# MB1296-STLINK.net
KiCad netlist of a schematic drawn in Altium Designer
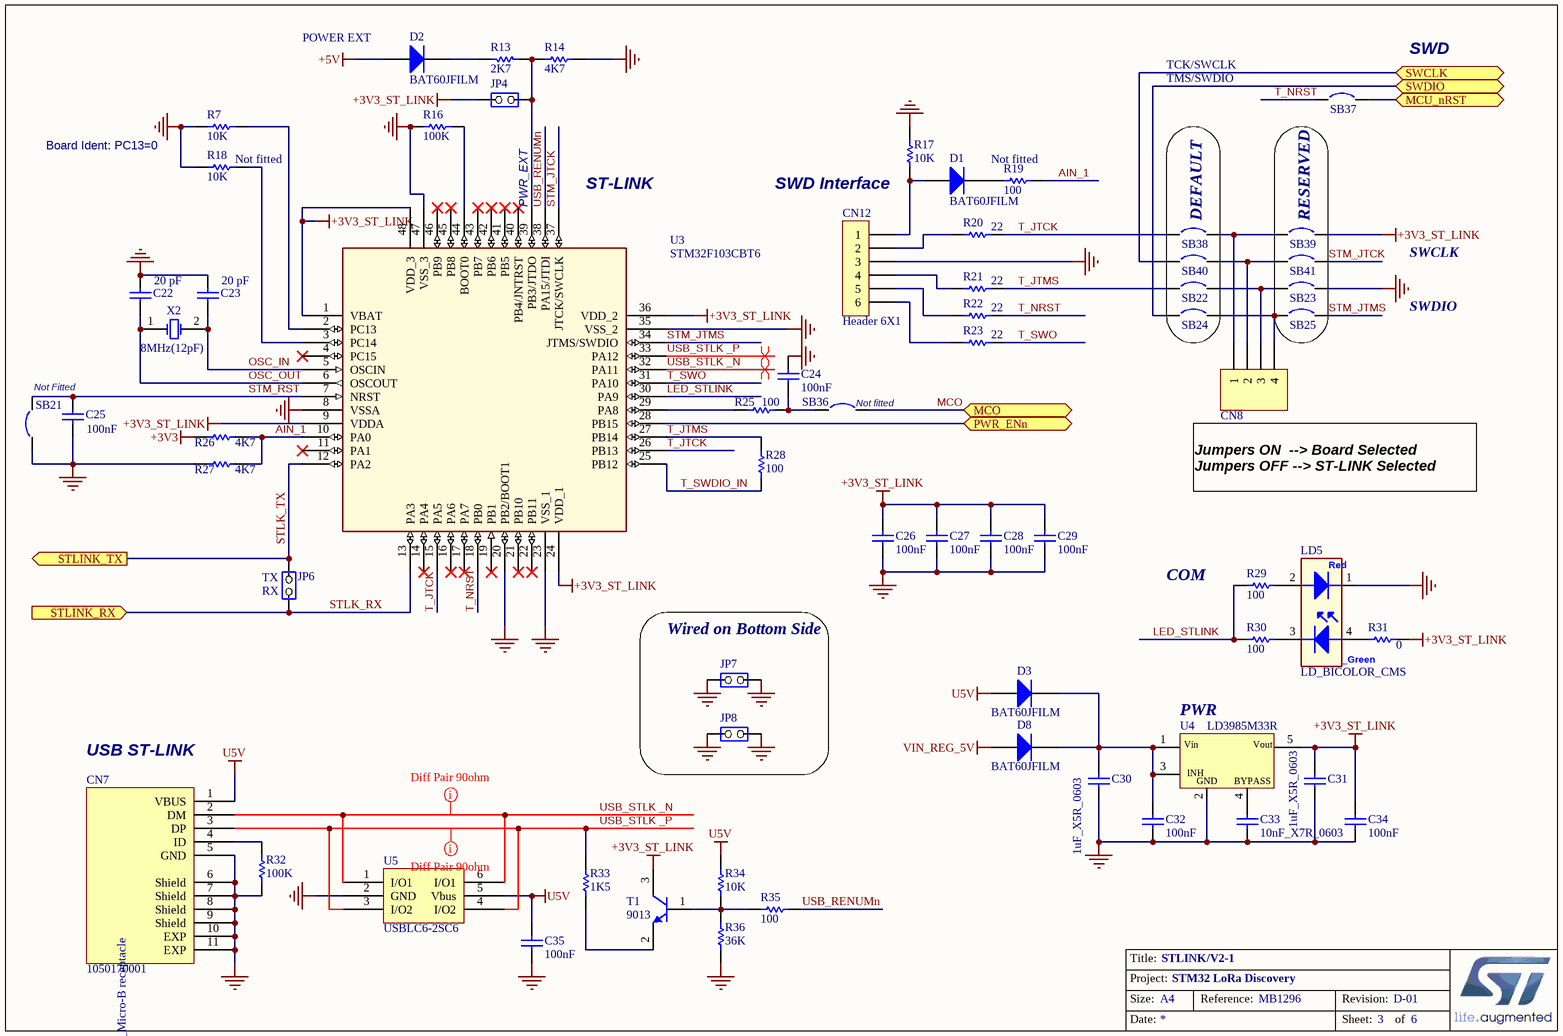
[diagram p0: MB1296-STLINK.SchDoc]

(export (version "E")
  (design (tool "Eeschema 10.0.6"))
  (components
    (comp (ref "C22")
      (value "20 pF")
      (footprint "0603C")
      (description "Capacitor 0603")
      (fields (field (name "MANUFACTURER") "YAGEO") (field (name "PROVIDED BY") "Subcon"))
      (libsource (lib "MCD16-033-STM32_LRA_Eval_Board_1") (part "Capacitor_ST"))
    )
    (comp (ref "C23")
      (value "20 pF")
      (footprint "0603C")
      (description "Capacitor 0603")
      (fields (field (name "MANUFACTURER") "YAGEO") (field (name "PROVIDED BY") "Subcon"))
      (libsource (lib "MCD16-033-STM32_LRA_Eval_Board_1") (part "Capacitor_ST"))
    )
    (comp (ref "C24")
      (value "100nF")
      (footprint "0603C")
      (description "Capacitor 100nF")
      (fields (field (name "MANUFACTURER") "YAGEO") (field (name "PROVIDED BY") "Subcon"))
      (libsource (lib "MCD16-033-STM32_LRA_Eval_Board_1") (part "CAP"))
    )
    (comp (ref "C25")
      (value "100nF")
      (footprint "0603C")
      (description "Capacitor 100nF")
      (fields (field (name "MANUFACTURER") "YAGEO") (field (name "PROVIDED BY") "Subcon"))
      (libsource (lib "MCD16-033-STM32_LRA_Eval_Board_1") (part "CAP"))
    )
    (comp (ref "C26")
      (value "100nF")
      (footprint "0603C")
      (description "Capacitor 100nF")
      (fields (field (name "MANUFACTURER") "YAGEO") (field (name "PROVIDED BY") "Subcon"))
      (libsource (lib "MCD16-033-STM32_LRA_Eval_Board_1") (part "CAP"))
    )
    (comp (ref "C27")
      (value "100nF")
      (footprint "0603C")
      (description "Capacitor 100nF")
      (fields (field (name "MANUFACTURER") "YAGEO") (field (name "PROVIDED BY") "Subcon"))
      (libsource (lib "MCD16-033-STM32_LRA_Eval_Board_1") (part "CAP"))
    )
    (comp (ref "C28")
      (value "100nF")
      (footprint "0603C")
      (description "Capacitor 100nF")
      (fields (field (name "MANUFACTURER") "YAGEO") (field (name "PROVIDED BY") "Subcon"))
      (libsource (lib "MCD16-033-STM32_LRA_Eval_Board_1") (part "CAP"))
    )
    (comp (ref "C29")
      (value "100nF")
      (footprint "0603C")
      (description "Capacitor 100nF")
      (fields (field (name "MANUFACTURER") "YAGEO") (field (name "PROVIDED BY") "Subcon"))
      (libsource (lib "MCD16-033-STM32_LRA_Eval_Board_1") (part "CAP"))
    )
    (comp (ref "C30")
      (value "1uF_X5R_0603")
      (footprint "0603C")
      (description "0603  X5R 1µF")
      (fields (field (name "MANUFACTURER") "YAGEO") (field (name "PROVIDED BY") "Subcon"))
      (libsource (lib "MCD16-033-STM32_LRA_Eval_Board_1") (part "CAP SMD 0603  X5R 1µF 25V 10%"))
    )
    (comp (ref "C31")
      (value "1uF_X5R_0603")
      (footprint "0603C")
      (description "0603  X5R 1µF")
      (fields (field (name "MANUFACTURER") "YAGEO") (field (name "PROVIDED BY") "Subcon"))
      (libsource (lib "MCD16-033-STM32_LRA_Eval_Board_1") (part "CAP SMD 0603  X5R 1µF 25V 10%"))
    )
    (comp (ref "C32")
      (value "100nF")
      (footprint "0603C")
      (description "Capacitor 100nF")
      (fields (field (name "MANUFACTURER") "YAGEO") (field (name "PROVIDED BY") "Subcon"))
      (libsource (lib "MCD16-033-STM32_LRA_Eval_Board_1") (part "CAP"))
    )
    (comp (ref "C33")
      (value "10nF_X7R_0603")
      (footprint "0603C")
      (description "0603  X7R 10NF")
      (fields (field (name "MANUFACTURER") "YAGEO") (field (name "PROVIDED BY") "Subcon"))
      (libsource (lib "MCD16-033-STM32_LRA_Eval_Board_1") (part "CAP SMD 0603  X7R 10000PF 50V 10%"))
    )
    (comp (ref "C34")
      (value "100nF")
      (footprint "0603C")
      (description "Capacitor 100nF")
      (fields (field (name "MANUFACTURER") "YAGEO") (field (name "PROVIDED BY") "Subcon"))
      (libsource (lib "MCD16-033-STM32_LRA_Eval_Board_1") (part "CAP"))
    )
    (comp (ref "C35")
      (value "100nF")
      (footprint "0603C")
      (description "Capacitor 100nF")
      (fields (field (name "MANUFACTURER") "YAGEO") (field (name "PROVIDED BY") "Subcon"))
      (libsource (lib "MCD16-033-STM32_LRA_Eval_Board_1") (part "CAP"))
    )
    (comp (ref "CN7")
      (value "1050170001")
      (footprint "Molex_1050170001")
      (libsource (lib "Smartphone_accessory") (part "1050170001"))
    )
    (comp (ref "CN8")
      (value "Header 4")
      (footprint "SIP4")
      (description "Header, 4-Pin, Single row")
      (fields (field (name "MANUFACTURER") "Lyconn") (field (name "PROVIDED BY") "Subcon"))
      (libsource (lib "MCD16-033-STM32_LRA_Eval_Board_1") (part "Header 4"))
    )
    (comp (ref "CN12")
      (value "Header 6X1")
      (footprint "Header 1x6 Female (Wrapping)")
      (description "Header, 6-Pin, Single row")
      (fields (field (name "MANUFACTURER") "Lyconn") (field (name "PROVIDED BY") "Subcon"))
      (libsource (lib "MCD16-033-STM32_LRA_Eval_Board_1") (part "Header 6X1"))
    )
    (comp (ref "D1")
      (value "BAT60JFILM")
      (footprint "SOD323/A")
      (fields (field (name "MANUFACTURER") "STM"))
      (libsource (lib "MCD16-033-STM32_LRA_Eval_Board_1") (part "BAT60JFILM"))
    )
    (comp (ref "D2")
      (value "BAT60JFILM")
      (footprint "SOD323/A")
      (fields (field (name "MANUFACTURER") "STM"))
      (libsource (lib "MCD16-033-STM32_LRA_Eval_Board_1") (part "BAT60JFILM"))
    )
    (comp (ref "D3")
      (value "BAT60JFILM")
      (footprint "SOD323/A")
      (fields (field (name "MANUFACTURER") "STM"))
      (libsource (lib "MCD16-033-STM32_LRA_Eval_Board_1") (part "BAT60JFILM"))
    )
    (comp (ref "D8")
      (value "BAT60JFILM")
      (footprint "SOD323/A")
      (fields (field (name "MANUFACTURER") "STM"))
      (libsource (lib "MCD16-033-STM32_LRA_Eval_Board_1") (part "BAT60JFILM"))
    )
    (comp (ref "JP4")
      (value "~")
      (footprint "SIP2/2.54")
      (fields (field (name "MANUFACTURER") "Lyconn") (field (name "PROVIDED BY") "Subcon"))
      (libsource (lib "MCD16-033-STM32_LRA_Eval_Board_1") (part "JP2"))
    )
    (comp (ref "JP6")
      (value "~")
      (footprint "SIP2/2.54")
      (fields (field (name "MANUFACTURER") "Lyconn") (field (name "PROVIDED BY") "Subcon"))
      (libsource (lib "MCD16-033-STM32_LRA_Eval_Board_1") (part "JP2"))
    )
    (comp (ref "JP7")
      (value "~")
      (footprint "SIP2/2.54-BOT")
      (fields (field (name "MANUFACTURER") "Lyconn") (field (name "PROVIDED BY") "Subcon"))
      (libsource (lib "MCD16-033-STM32_LRA_Eval_Board_1") (part "JP2"))
    )
    (comp (ref "JP8")
      (value "~")
      (footprint "SIP2/2.54-BOT")
      (fields (field (name "MANUFACTURER") "Lyconn") (field (name "PROVIDED BY") "Subcon"))
      (libsource (lib "MCD16-033-STM32_LRA_Eval_Board_1") (part "JP2"))
    )
    (comp (ref "LD5")
      (value "LD_BICOLOR_CMS")
      (footprint "LED SMD HSMF-A201-A00J1")
      (description "Bicolor Led")
      (fields (field (name "MANUFACTURER") "everluck-led") (field (name "PROVIDED BY") "Subcon"))
      (libsource (lib "MCD16-033-STM32_LRA_Eval_Board_1") (part "LD_BICOLOR_CMS"))
    )
    (comp (ref "R7")
      (value "10K")
      (footprint "0603")
      (description "Resistor 0603")
      (fields (field (name "MANUFACTURER") "YAGEO") (field (name "PROVIDED BY") "Subcon"))
      (libsource (lib "MCD16-033-STM32_LRA_Eval_Board_1") (part "Resistor_ST"))
    )
    (comp (ref "R13")
      (value "2K7")
      (description "Resistor")
      (fields (field (name "PUBLISHER") "Altium Limited"))
      (libsource (lib "Miscellaneous Devices") (part "Res1"))
    )
    (comp (ref "R14")
      (value "4K7")
      (description "Resistor")
      (fields (field (name "MANUFACTURER") "YAGEO") (field (name "PROVIDED BY") "Subcon"))
      (libsource (lib "MCD16-033-STM32_LRA_Eval_Board_1") (part "res1_4"))
    )
    (comp (ref "R16")
      (value "100K")
      (footprint "0603")
      (description "0603 100K 75V 5% 0.1W")
      (fields (field (name "MANUFACTURER") "YAGEO") (field (name "PROVIDED BY") "Subcon"))
      (libsource (lib "MCD16-033-STM32_LRA_Eval_Board_1") (part "RES SMD 0603 100K 75V 5% 0.1W"))
    )
    (comp (ref "R17")
      (value "10K")
      (footprint "0603")
      (description "Resistor 0603")
      (fields (field (name "MANUFACTURER") "YAGEO") (field (name "PROVIDED BY") "Subcon"))
      (libsource (lib "MCD16-033-STM32_LRA_Eval_Board_1") (part "Resistor_ST"))
    )
    (comp (ref "R18")
      (value "10K")
      (footprint "0603")
      (description "Resistor 0603")
      (fields (field (name "MANUFACTURER") "YAGEO") (field (name "PROVIDED BY") "Subcon"))
      (libsource (lib "MCD16-033-STM32_LRA_Eval_Board_1") (part "Resistor_ST"))
    )
    (comp (ref "R19")
      (value "100")
      (footprint "0603")
      (description "Resistor 0603")
      (fields (field (name "MANUFACTURER") "YAGEO") (field (name "PROVIDED BY") "Subcon"))
      (libsource (lib "MCD16-033-STM32_LRA_Eval_Board_1") (part "Res1_1"))
    )
    (comp (ref "R20")
      (value "22")
      (footprint "0603")
      (description "Resistor 0603")
      (fields (field (name "MANUFACTURER") "YAGEO") (field (name "PROVIDED BY") "Subcon"))
      (libsource (lib "MCD16-033-STM32_LRA_Eval_Board_1") (part "Res1_1"))
    )
    (comp (ref "R21")
      (value "22")
      (footprint "0603")
      (description "Resistor 0603")
      (fields (field (name "MANUFACTURER") "YAGEO") (field (name "PROVIDED BY") "Subcon"))
      (libsource (lib "MCD16-033-STM32_LRA_Eval_Board_1") (part "Res1_1"))
    )
    (comp (ref "R22")
      (value "22")
      (footprint "0603")
      (description "Resistor 0603")
      (fields (field (name "MANUFACTURER") "YAGEO") (field (name "PROVIDED BY") "Subcon"))
      (libsource (lib "MCD16-033-STM32_LRA_Eval_Board_1") (part "Res1_1"))
    )
    (comp (ref "R23")
      (value "22")
      (footprint "0603")
      (description "Resistor 0603")
      (fields (field (name "MANUFACTURER") "YAGEO") (field (name "PROVIDED BY") "Subcon"))
      (libsource (lib "MCD16-033-STM32_LRA_Eval_Board_1") (part "Res1_1"))
    )
    (comp (ref "R25")
      (value "100")
      (footprint "0603")
      (description "Resistor 0603")
      (fields (field (name "MANUFACTURER") "YAGEO") (field (name "PROVIDED BY") "Subcon"))
      (libsource (lib "MCD16-033-STM32_LRA_Eval_Board_1") (part "Res1_1"))
    )
    (comp (ref "R26")
      (value "4K7")
      (description "Resistor")
      (fields (field (name "MANUFACTURER") "YAGEO") (field (name "PROVIDED BY") "Subcon"))
      (libsource (lib "MCD16-033-STM32_LRA_Eval_Board_1") (part "res1_4"))
    )
    (comp (ref "R27")
      (value "4K7")
      (description "Resistor")
      (fields (field (name "MANUFACTURER") "YAGEO") (field (name "PROVIDED BY") "Subcon"))
      (libsource (lib "MCD16-033-STM32_LRA_Eval_Board_1") (part "res1_4"))
    )
    (comp (ref "R28")
      (value "100")
      (footprint "0603")
      (description "Resistor 0603")
      (fields (field (name "MANUFACTURER") "YAGEO") (field (name "PROVIDED BY") "Subcon"))
      (libsource (lib "MCD16-033-STM32_LRA_Eval_Board_1") (part "Res1_1"))
    )
    (comp (ref "R29")
      (value "100")
      (footprint "0603")
      (description "Resistor 0603")
      (fields (field (name "MANUFACTURER") "YAGEO") (field (name "PROVIDED BY") "Subcon"))
      (libsource (lib "MCD16-033-STM32_LRA_Eval_Board_1") (part "Res1_1"))
    )
    (comp (ref "R30")
      (value "100")
      (footprint "0603")
      (description "Resistor 0603")
      (fields (field (name "MANUFACTURER") "YAGEO") (field (name "PROVIDED BY") "Subcon"))
      (libsource (lib "MCD16-033-STM32_LRA_Eval_Board_1") (part "Res1_1"))
    )
    (comp (ref "R31")
      (value "0")
      (footprint "0603")
      (description "Resistor 0402 / 0603 / 0805")
      (libsource (lib "") (part "Res1_2"))
    )
    (comp (ref "R32")
      (value "100K")
      (footprint "0603")
      (description "0603 100K 75V 5% 0.1W")
      (fields (field (name "MANUFACTURER") "YAGEO") (field (name "PROVIDED BY") "Subcon"))
      (libsource (lib "MCD16-033-STM32_LRA_Eval_Board_1") (part "RES SMD 0603 100K 75V 5% 0.1W"))
    )
    (comp (ref "R33")
      (value "1K5")
      (footprint "0603")
      (description "0603 1K5 75V 5% 0.1W")
      (fields (field (name "MANUFACTURER") "YAGEO") (field (name "PROVIDED BY") "Subcon"))
      (libsource (lib "MCD16-033-STM32_LRA_Eval_Board_1") (part "RES SMD 0603 100K 75V 5% 0.1W"))
    )
    (comp (ref "R34")
      (value "10K")
      (footprint "0603")
      (description "Resistor 0603")
      (fields (field (name "MANUFACTURER") "YAGEO") (field (name "PROVIDED BY") "Subcon"))
      (libsource (lib "MCD16-033-STM32_LRA_Eval_Board_1") (part "Resistor_ST"))
    )
    (comp (ref "R35")
      (value "100")
      (footprint "0603")
      (description "Resistor 0603")
      (fields (field (name "MANUFACTURER") "YAGEO") (field (name "PROVIDED BY") "Subcon"))
      (libsource (lib "MCD16-033-STM32_LRA_Eval_Board_1") (part "Res1_1"))
    )
    (comp (ref "R36")
      (value "36K")
      (description "Resistor")
      (fields (field (name "PUBLISHER") "Altium Limited"))
      (libsource (lib "") (part "Res1_1"))
    )
    (comp (ref "SB21")
      (value "Circuit Breaker")
      (footprint "JP2_SMD")
      (libsource (lib "MCD16-033-STM32_LRA_Eval_Board_1") (part "Circuit Breaker"))
    )
    (comp (ref "SB22")
      (value "Circuit Breaker")
      (footprint "JP2_SMD")
      (libsource (lib "MCD16-033-STM32_LRA_Eval_Board_1") (part "Circuit Breaker"))
    )
    (comp (ref "SB23")
      (value "Circuit Breaker")
      (footprint "SB-tiny")
      (libsource (lib "MCD16-033-STM32_LRA_Eval_Board_1") (part "Circuit Breaker"))
    )
    (comp (ref "SB24")
      (value "Circuit Breaker")
      (footprint "JP2_SMD")
      (libsource (lib "MCD16-033-STM32_LRA_Eval_Board_1") (part "Circuit Breaker"))
    )
    (comp (ref "SB25")
      (value "Circuit Breaker")
      (footprint "SB-tiny")
      (libsource (lib "MCD16-033-STM32_LRA_Eval_Board_1") (part "Circuit Breaker"))
    )
    (comp (ref "SB36")
      (value "Circuit Breaker")
      (footprint "JP2_SMD")
      (libsource (lib "MCD16-033-STM32_LRA_Eval_Board_1") (part "Circuit Breaker"))
    )
    (comp (ref "SB37")
      (value "Circuit Breaker")
      (footprint "JP2_SMD")
      (libsource (lib "MCD16-033-STM32_LRA_Eval_Board_1") (part "Circuit Breaker"))
    )
    (comp (ref "SB38")
      (value "Circuit Breaker")
      (footprint "JP2_SMD")
      (libsource (lib "MCD16-033-STM32_LRA_Eval_Board_1") (part "Circuit Breaker"))
    )
    (comp (ref "SB39")
      (value "Circuit Breaker")
      (footprint "SB-tiny")
      (libsource (lib "MCD16-033-STM32_LRA_Eval_Board_1") (part "Circuit Breaker"))
    )
    (comp (ref "SB40")
      (value "Circuit Breaker")
      (footprint "JP2_SMD")
      (libsource (lib "MCD16-033-STM32_LRA_Eval_Board_1") (part "Circuit Breaker"))
    )
    (comp (ref "SB41")
      (value "Circuit Breaker")
      (footprint "SB-tiny")
      (libsource (lib "MCD16-033-STM32_LRA_Eval_Board_1") (part "Circuit Breaker"))
    )
    (comp (ref "T1")
      (value "9013")
      (footprint "SOT-23")
      (description "NPN Bipolar Transistor")
      (fields (field (name "MANUFACTURER") "STMicroelectronics") (field (name "PROVIDED BY") "STM"))
      (libsource (lib "MB1167") (part "NPN"))
    )
    (comp (ref "U3")
      (value "STM32F103CBT6")
      (footprint "QFP48 7X7")
      (description "Medium-density performance line ARM-based 32-bit MCU with 64KB Flash")
      (fields (field (name "MANUFACTURER") "STM"))
      (libsource (lib "Nucleo_64") (part "STM32F103CBT6"))
    )
    (comp (ref "U4")
      (value "LD3985M33R")
      (footprint "SOT-23-5L")
      (description "Ultra low drop-low noise BiCMOS voltage, regulators low ESR capacitors compatible")
      (fields (field (name "MANUFACTURER") "STM") (field (name "PROVIDED BY") "STM"))
      (libsource (lib "MCD16-033-STM32_LRA_Eval_Board_1") (part "LD3985M33R"))
    )
    (comp (ref "U5")
      (value "USBLC6-2SC6")
      (footprint "SOT23-6L")
      (fields (field (name "MANUFACTURER") "STMicroelectronics") (field (name "PROVIDED BY") "STM"))
      (libsource (lib "MB1137") (part "USBLC6-2SC6"))
    )
    (comp (ref "X2")
      (value "8MHz(12pF)")
      (footprint "CRY_NX3225GD_2P")
      (description "Crystal Oscillator")
      (fields (field (name "MANUFACTURER") "HongKongCrystal") (field (name "PROVIDED BY") "Subcon"))
      (libsource (lib "MB963_1") (part "XTAL"))
    )
  )
  (nets
    (net (code "1") (name "+3V3") (class "Default")
      (node (ref "R26") (pin "1") (pinfunction "1_1") (pintype "passive"))
    )
    (net (code "2") (name "+3V3_ST_LINK") (class "Default")
      (node (ref "C26") (pin "2") (pinfunction "2_2") (pintype "passive"))
      (node (ref "C27") (pin "2") (pinfunction "2_2") (pintype "passive"))
      (node (ref "C28") (pin "2") (pinfunction "2_2") (pintype "passive"))
      (node (ref "C29") (pin "2") (pinfunction "2_2") (pintype "passive"))
      (node (ref "C31") (pin "2") (pinfunction "2_2") (pintype "passive"))
      (node (ref "C34") (pin "2") (pinfunction "2_2") (pintype "passive"))
      (node (ref "JP4") (pin "1") (pinfunction "COMMON_1") (pintype "passive"))
      (node (ref "R31") (pin "2") (pinfunction "2_2") (pintype "passive"))
      (node (ref "SB39") (pin "2") (pinfunction "2_2") (pintype "passive"))
      (node (ref "T1") (pin "3") (pinfunction "C_3") (pintype "passive"))
      (node (ref "U3") (pin "1") (pinfunction "VBAT_1") (pintype "power_in"))
      (node (ref "U3") (pin "24") (pinfunction "VDD_1_24") (pintype "power_in"))
      (node (ref "U3") (pin "36") (pinfunction "VDD_2_36") (pintype "power_in"))
      (node (ref "U3") (pin "48") (pinfunction "VDD_3_48") (pintype "power_in"))
      (node (ref "U3") (pin "9") (pinfunction "VDDA_9") (pintype "power_in"))
      (node (ref "U4") (pin "5") (pinfunction "Vout_5") (pintype "passive"))
    )
    (net (code "3") (name "+5V") (class "Default")
      (node (ref "D2") (pin "1") (pinfunction "A_1") (pintype "passive"))
    )
    (net (code "4") (name "/AIN_1") (class "Default")
      (node (ref "R19") (pin "1") (pinfunction "1_1") (pintype "passive"))
      (node (ref "R26") (pin "2") (pinfunction "2_2") (pintype "passive"))
      (node (ref "R27") (pin "2") (pinfunction "2_2") (pintype "passive"))
      (node (ref "U3") (pin "10") (pinfunction "PA0_10") (pintype "bidirectional"))
    )
    (net (code "5") (name "/LED_STLINK") (class "Default")
      (node (ref "R29") (pin "2") (pinfunction "2_2") (pintype "passive"))
      (node (ref "R30") (pin "2") (pinfunction "2_2") (pintype "passive"))
      (node (ref "U3") (pin "30") (pinfunction "PA9_30") (pintype "bidirectional"))
    )
    (net (code "6") (name "/MCO") (class "Default")
      (node (ref "SB36") (pin "2") (pinfunction "2_2") (pintype "passive"))
    )
    (net (code "7") (name "/MCU_nRST") (class "Default")
      (node (ref "SB37") (pin "2") (pinfunction "2_2") (pintype "passive"))
    )
    (net (code "8") (name "/OSC_IN") (class "Default")
      (node (ref "C23") (pin "1") (pinfunction "1_1") (pintype "passive"))
      (node (ref "U3") (pin "5") (pinfunction "OSCIN_5") (pintype "input"))
      (node (ref "X2") (pin "2") (pinfunction "OSC2_2") (pintype "passive"))
    )
    (net (code "9") (name "/OSC_OUT") (class "Default")
      (node (ref "C22") (pin "1") (pinfunction "1_1") (pintype "passive"))
      (node (ref "U3") (pin "6") (pinfunction "OSCOUT_6") (pintype "output"))
      (node (ref "X2") (pin "1") (pinfunction "OSC1_1") (pintype "passive"))
    )
    (net (code "10") (name "/PWR_ENn") (class "Default")
      (node (ref "U3") (pin "28") (pinfunction "PB15_28") (pintype "bidirectional"))
    )
    (net (code "11") (name "/STLK_RX") (class "Default")
      (node (ref "JP6") (pin "1") (pinfunction "COMMON_1") (pintype "passive"))
      (node (ref "U3") (pin "13") (pinfunction "PA3_13") (pintype "bidirectional"))
    )
    (net (code "12") (name "/STLK_TX") (class "Default")
      (node (ref "JP6") (pin "2") (pinfunction "NO_2") (pintype "passive"))
      (node (ref "U3") (pin "12") (pinfunction "PA2_12") (pintype "bidirectional"))
    )
    (net (code "13") (name "/STM_JTCK") (class "Default")
      (node (ref "SB41") (pin "2") (pinfunction "2_2") (pintype "passive"))
      (node (ref "U3") (pin "37") (pinfunction "JTCK/SWCLK_37") (pintype "bidirectional"))
    )
    (net (code "14") (name "/STM_JTMS") (class "Default")
      (node (ref "SB25") (pin "2") (pinfunction "2_2") (pintype "passive"))
      (node (ref "U3") (pin "34") (pinfunction "JTMS/SWDIO_34") (pintype "bidirectional"))
    )
    (net (code "15") (name "/STM_RST") (class "Default")
      (node (ref "C25") (pin "2") (pinfunction "2_2") (pintype "passive"))
      (node (ref "SB21") (pin "2") (pinfunction "2_2") (pintype "passive"))
      (node (ref "U3") (pin "7") (pinfunction "NRST_7") (pintype "input"))
    )
    (net (code "16") (name "/SWCLK") (class "Default")
      (node (ref "SB40") (pin "1") (pinfunction "1_1") (pintype "passive"))
    )
    (net (code "17") (name "/SWDIO") (class "Default")
      (node (ref "SB24") (pin "1") (pinfunction "1_1") (pintype "passive"))
    )
    (net (code "18") (name "/T_JTCK") (class "Default")
      (node (ref "R20") (pin "1") (pinfunction "1_1") (pintype "passive"))
      (node (ref "SB38") (pin "1") (pinfunction "1_1") (pintype "passive"))
      (node (ref "U3") (pin "15") (pinfunction "PA5_15") (pintype "bidirectional"))
      (node (ref "U3") (pin "26") (pinfunction "PB13_26") (pintype "bidirectional"))
    )
    (net (code "19") (name "/T_JTMS") (class "Default")
      (node (ref "R21") (pin "1") (pinfunction "1_1") (pintype "passive"))
      (node (ref "R28") (pin "2") (pinfunction "2_2") (pintype "passive"))
      (node (ref "SB22") (pin "1") (pinfunction "1_1") (pintype "passive"))
      (node (ref "U3") (pin "27") (pinfunction "PB14_27") (pintype "bidirectional"))
    )
    (net (code "20") (name "/T_NRST") (class "Default")
      (node (ref "R22") (pin "1") (pinfunction "1_1") (pintype "passive"))
      (node (ref "SB37") (pin "1") (pinfunction "1_1") (pintype "passive"))
      (node (ref "U3") (pin "18") (pinfunction "PB0_18") (pintype "bidirectional"))
    )
    (net (code "21") (name "/T_SWDIO_IN") (class "Default")
      (node (ref "R28") (pin "1") (pinfunction "1_1") (pintype "passive"))
      (node (ref "U3") (pin "25") (pinfunction "PB12_25") (pintype "bidirectional"))
    )
    (net (code "22") (name "/T_SWO") (class "Default")
      (node (ref "R23") (pin "1") (pinfunction "1_1") (pintype "passive"))
      (node (ref "U3") (pin "31") (pinfunction "PA10_31") (pintype "bidirectional"))
    )
    (net (code "23") (name "/USB_RENUMn") (class "Default")
      (node (ref "R35") (pin "1") (pinfunction "1_1") (pintype "passive"))
      (node (ref "U3") (pin "38") (pinfunction "PA15/JTDI_38") (pintype "bidirectional"))
    )
    (net (code "24") (name "/USB_STLK _N") (class "Default")
      (node (ref "CN7") (pin "2") (pinfunction "DM_2") (pintype "passive"))
      (node (ref "U3") (pin "32") (pinfunction "PA11_32") (pintype "bidirectional"))
      (node (ref "U5") (pin "1") (pinfunction "I/O1_1") (pintype "passive"))
      (node (ref "U5") (pin "6") (pinfunction "I/O1_6") (pintype "passive"))
    )
    (net (code "25") (name "/USB_STLK _P") (class "Default")
      (node (ref "CN7") (pin "3") (pinfunction "DP_3") (pintype "passive"))
      (node (ref "R33") (pin "2") (pinfunction "2_2") (pintype "passive"))
      (node (ref "U3") (pin "33") (pinfunction "PA12_33") (pintype "bidirectional"))
      (node (ref "U5") (pin "3") (pinfunction "I/O2_3") (pintype "passive"))
      (node (ref "U5") (pin "4") (pinfunction "I/O2_4") (pintype "passive"))
    )
    (net (code "26") (name "GND") (class "Default")
      (node (ref "C22") (pin "2") (pinfunction "2_2") (pintype "passive"))
      (node (ref "C23") (pin "2") (pinfunction "2_2") (pintype "passive"))
      (node (ref "C24") (pin "2") (pinfunction "2_2") (pintype "passive"))
      (node (ref "C25") (pin "1") (pinfunction "1_1") (pintype "passive"))
      (node (ref "C26") (pin "1") (pinfunction "1_1") (pintype "passive"))
      (node (ref "C27") (pin "1") (pinfunction "1_1") (pintype "passive"))
      (node (ref "C28") (pin "1") (pinfunction "1_1") (pintype "passive"))
      (node (ref "C29") (pin "1") (pinfunction "1_1") (pintype "passive"))
      (node (ref "C30") (pin "1") (pinfunction "1_1") (pintype "passive"))
      (node (ref "C31") (pin "1") (pinfunction "1_1") (pintype "passive"))
      (node (ref "C32") (pin "1") (pinfunction "1_1") (pintype "passive"))
      (node (ref "C33") (pin "1") (pinfunction "1_1") (pintype "passive"))
      (node (ref "C34") (pin "1") (pinfunction "1_1") (pintype "passive"))
      (node (ref "C35") (pin "1") (pinfunction "1_1") (pintype "passive"))
      (node (ref "CN12") (pin "3") (pinfunction "3_3") (pintype "passive"))
      (node (ref "CN7") (pin "10") (pinfunction "EXP_10") (pintype "passive"))
      (node (ref "CN7") (pin "11") (pinfunction "EXP_11") (pintype "passive"))
      (node (ref "CN7") (pin "5") (pinfunction "GND_5") (pintype "passive"))
      (node (ref "CN7") (pin "6") (pinfunction "Shield_6") (pintype "passive"))
      (node (ref "CN7") (pin "7") (pinfunction "Shield_7") (pintype "passive"))
      (node (ref "CN7") (pin "8") (pinfunction "Shield_8") (pintype "passive"))
      (node (ref "CN7") (pin "9") (pinfunction "Shield_9") (pintype "passive"))
      (node (ref "JP7") (pin "1") (pinfunction "COMMON_1") (pintype "passive"))
      (node (ref "JP7") (pin "2") (pinfunction "NO_2") (pintype "passive"))
      (node (ref "JP8") (pin "1") (pinfunction "COMMON_1") (pintype "passive"))
      (node (ref "JP8") (pin "2") (pinfunction "NO_2") (pintype "passive"))
      (node (ref "LD5") (pin "1") (pinfunction "1_1") (pintype "passive"))
      (node (ref "R14") (pin "2") (pinfunction "2_2") (pintype "passive"))
      (node (ref "R16") (pin "2") (pinfunction "2_2") (pintype "passive"))
      (node (ref "R17") (pin "1") (pinfunction "1_1") (pintype "passive"))
      (node (ref "R18") (pin "2") (pinfunction "2_2") (pintype "passive"))
      (node (ref "R27") (pin "1") (pinfunction "1_1") (pintype "passive"))
      (node (ref "R32") (pin "1") (pinfunction "1_1") (pintype "passive"))
      (node (ref "R36") (pin "1") (pinfunction "1_1") (pintype "passive"))
      (node (ref "R7") (pin "2") (pinfunction "2_2") (pintype "passive"))
      (node (ref "SB21") (pin "1") (pinfunction "1_1") (pintype "passive"))
      (node (ref "SB23") (pin "2") (pinfunction "2_2") (pintype "passive"))
      (node (ref "U3") (pin "20") (pinfunction "PB2/BOOT1_20") (pintype "bidirectional"))
      (node (ref "U3") (pin "23") (pinfunction "VSS_1_23") (pintype "power_in"))
      (node (ref "U3") (pin "35") (pinfunction "VSS_2_35") (pintype "power_in"))
      (node (ref "U3") (pin "47") (pinfunction "VSS_3_47") (pintype "power_in"))
      (node (ref "U3") (pin "8") (pinfunction "VSSA_8") (pintype "power_in"))
      (node (ref "U4") (pin "2") (pinfunction "GND_2") (pintype "passive"))
      (node (ref "U5") (pin "2") (pinfunction "GND_2") (pintype "passive"))
    )
    (net (code "27") (name "Net-(C24-Pad1)") (class "Default")
      (node (ref "C24") (pin "1") (pinfunction "1_1") (pintype "passive"))
      (node (ref "R25") (pin "1") (pinfunction "1_1") (pintype "passive"))
      (node (ref "SB36") (pin "1") (pinfunction "1_1") (pintype "passive"))
    )
    (net (code "28") (name "Net-(CN7-ID)") (class "Default")
      (node (ref "CN7") (pin "4") (pinfunction "ID_4") (pintype "passive"))
      (node (ref "R32") (pin "2") (pinfunction "2_2") (pintype "passive"))
    )
    (net (code "29") (name "Net-(CN8-Pad1)") (class "Default")
      (node (ref "CN8") (pin "1") (pinfunction "1_1") (pintype "passive"))
      (node (ref "SB38") (pin "2") (pinfunction "2_2") (pintype "passive"))
      (node (ref "SB39") (pin "1") (pinfunction "1_1") (pintype "passive"))
    )
    (net (code "30") (name "Net-(CN8-Pad2)") (class "Default")
      (node (ref "CN8") (pin "2") (pinfunction "2_2") (pintype "passive"))
      (node (ref "SB40") (pin "2") (pinfunction "2_2") (pintype "passive"))
      (node (ref "SB41") (pin "1") (pinfunction "1_1") (pintype "passive"))
    )
    (net (code "31") (name "Net-(CN8-Pad3)") (class "Default")
      (node (ref "CN8") (pin "3") (pinfunction "3_3") (pintype "passive"))
      (node (ref "SB22") (pin "2") (pinfunction "2_2") (pintype "passive"))
      (node (ref "SB23") (pin "1") (pinfunction "1_1") (pintype "passive"))
    )
    (net (code "32") (name "Net-(CN8-Pad4)") (class "Default")
      (node (ref "CN8") (pin "4") (pinfunction "4_4") (pintype "passive"))
      (node (ref "SB24") (pin "2") (pinfunction "2_2") (pintype "passive"))
      (node (ref "SB25") (pin "1") (pinfunction "1_1") (pintype "passive"))
    )
    (net (code "33") (name "Net-(CN12-Pad2)") (class "Default")
      (node (ref "CN12") (pin "2") (pinfunction "2_2") (pintype "passive"))
      (node (ref "R20") (pin "2") (pinfunction "2_2") (pintype "passive"))
    )
    (net (code "34") (name "Net-(CN12-Pad4)") (class "Default")
      (node (ref "CN12") (pin "4") (pinfunction "4_4") (pintype "passive"))
      (node (ref "R21") (pin "2") (pinfunction "2_2") (pintype "passive"))
    )
    (net (code "35") (name "Net-(CN12-Pad5)") (class "Default")
      (node (ref "CN12") (pin "5") (pinfunction "5_5") (pintype "passive"))
      (node (ref "R22") (pin "2") (pinfunction "2_2") (pintype "passive"))
    )
    (net (code "36") (name "Net-(CN12-Pad6)") (class "Default")
      (node (ref "CN12") (pin "6") (pinfunction "6_6") (pintype "passive"))
      (node (ref "R23") (pin "2") (pinfunction "2_2") (pintype "passive"))
    )
    (net (code "37") (name "Net-(D1-A)") (class "Default")
      (node (ref "CN12") (pin "1") (pinfunction "1_1") (pintype "passive"))
      (node (ref "D1") (pin "1") (pinfunction "A_1") (pintype "passive"))
      (node (ref "R17") (pin "2") (pinfunction "2_2") (pintype "passive"))
    )
    (net (code "38") (name "Net-(D1-K)") (class "Default")
      (node (ref "D1") (pin "2") (pinfunction "K_2") (pintype "passive"))
      (node (ref "R19") (pin "2") (pinfunction "2_2") (pintype "passive"))
    )
    (net (code "39") (name "Net-(D2-K)") (class "Default")
      (node (ref "D2") (pin "2") (pinfunction "K_2") (pintype "passive"))
      (node (ref "R13") (pin "1") (pinfunction "1_1") (pintype "passive"))
    )
    (net (code "40") (name "Net-(D3-K)") (class "Default")
      (node (ref "C30") (pin "2") (pinfunction "2_2") (pintype "passive"))
      (node (ref "C32") (pin "2") (pinfunction "2_2") (pintype "passive"))
      (node (ref "D3") (pin "2") (pinfunction "K_2") (pintype "passive"))
      (node (ref "D8") (pin "2") (pinfunction "K_2") (pintype "passive"))
      (node (ref "U4") (pin "1") (pinfunction "Vin_1") (pintype "passive"))
      (node (ref "U4") (pin "3") (pinfunction "CE_3") (pintype "passive"))
    )
    (net (code "41") (name "Net-(JP4-NO)") (class "Default")
      (node (ref "JP4") (pin "2") (pinfunction "NO_2") (pintype "passive"))
      (node (ref "R13") (pin "2") (pinfunction "2_2") (pintype "passive"))
      (node (ref "R14") (pin "1") (pinfunction "1_1") (pintype "passive"))
      (node (ref "U3") (pin "39") (pinfunction "PB3/JTDO_39") (pintype "bidirectional"))
    )
    (net (code "42") (name "Net-(LD5-Pad2)") (class "Default")
      (node (ref "LD5") (pin "2") (pinfunction "2_2") (pintype "passive"))
      (node (ref "R29") (pin "1") (pinfunction "1_1") (pintype "passive"))
    )
    (net (code "43") (name "Net-(LD5-Pad3)") (class "Default")
      (node (ref "LD5") (pin "3") (pinfunction "3_3") (pintype "passive"))
      (node (ref "R30") (pin "1") (pinfunction "1_1") (pintype "passive"))
    )
    (net (code "44") (name "Net-(LD5-Pad4)") (class "Default")
      (node (ref "LD5") (pin "4") (pinfunction "4_4") (pintype "passive"))
      (node (ref "R31") (pin "1") (pinfunction "1_1") (pintype "passive"))
    )
    (net (code "45") (name "Net-(T1-B)") (class "Default")
      (node (ref "R34") (pin "2") (pinfunction "2_2") (pintype "passive"))
      (node (ref "R35") (pin "2") (pinfunction "2_2") (pintype "passive"))
      (node (ref "R36") (pin "2") (pinfunction "2_2") (pintype "passive"))
      (node (ref "T1") (pin "1") (pinfunction "B_1") (pintype "passive"))
    )
    (net (code "46") (name "Net-(T1-E)") (class "Default")
      (node (ref "R33") (pin "1") (pinfunction "1_1") (pintype "passive"))
      (node (ref "T1") (pin "2") (pinfunction "E_2") (pintype "passive"))
    )
    (net (code "47") (name "Net-(U3-BOOT0)") (class "Default")
      (node (ref "R16") (pin "1") (pinfunction "1_1") (pintype "passive"))
      (node (ref "U3") (pin "44") (pinfunction "BOOT0_44") (pintype "bidirectional"))
    )
    (net (code "48") (name "Net-(U3-PA8)") (class "Default")
      (node (ref "R25") (pin "2") (pinfunction "2_2") (pintype "passive"))
      (node (ref "U3") (pin "29") (pinfunction "PA8_29") (pintype "bidirectional"))
    )
    (net (code "49") (name "Net-(U3-PC13)") (class "Default")
      (node (ref "R7") (pin "1") (pinfunction "1_1") (pintype "passive"))
      (node (ref "U3") (pin "2") (pinfunction "PC13_2") (pintype "bidirectional"))
    )
    (net (code "50") (name "Net-(U3-PC14)") (class "Default")
      (node (ref "R18") (pin "1") (pinfunction "1_1") (pintype "passive"))
      (node (ref "U3") (pin "3") (pinfunction "PC14_3") (pintype "bidirectional"))
    )
    (net (code "51") (name "Net-(U4-BYPASS)") (class "Default")
      (node (ref "C33") (pin "2") (pinfunction "2_2") (pintype "passive"))
      (node (ref "U4") (pin "4") (pinfunction "BYPASS_4") (pintype "passive"))
    )
    (net (code "52") (name "U5V") (class "Default")
      (node (ref "C35") (pin "2") (pinfunction "2_2") (pintype "passive"))
      (node (ref "CN7") (pin "1") (pinfunction "VBUS_1") (pintype "passive"))
      (node (ref "D3") (pin "1") (pinfunction "A_1") (pintype "passive"))
      (node (ref "R34") (pin "1") (pinfunction "1_1") (pintype "passive"))
      (node (ref "U5") (pin "5") (pinfunction "Vbus_5") (pintype "passive"))
    )
    (net (code "53") (name "VIN_REG_5V") (class "Default")
      (node (ref "D8") (pin "1") (pinfunction "A_1") (pintype "passive"))
    )
    (net (code "54") (name "unconnected-(U3-PA1-Pad11)") (class "Default")
      (node (ref "U3") (pin "11") (pinfunction "PA1_11") (pintype "bidirectional+no_connect"))
    )
    (net (code "55") (name "unconnected-(U3-PA4-Pad14)") (class "Default")
      (node (ref "U3") (pin "14") (pinfunction "PA4_14") (pintype "bidirectional+no_connect"))
    )
    (net (code "56") (name "unconnected-(U3-PA6-Pad16)") (class "Default")
      (node (ref "U3") (pin "16") (pinfunction "PA6_16") (pintype "bidirectional+no_connect"))
    )
    (net (code "57") (name "unconnected-(U3-PA7-Pad17)") (class "Default")
      (node (ref "U3") (pin "17") (pinfunction "PA7_17") (pintype "bidirectional+no_connect"))
    )
    (net (code "58") (name "unconnected-(U3-PB1-Pad19)") (class "Default")
      (node (ref "U3") (pin "19") (pinfunction "PB1_19") (pintype "input+no_connect"))
    )
    (net (code "59") (name "unconnected-(U3-PB4{slash}JNTRST-Pad40)") (class "Default")
      (node (ref "U3") (pin "40") (pinfunction "PB4/JNTRST_40") (pintype "bidirectional+no_connect"))
    )
    (net (code "60") (name "unconnected-(U3-PB5-Pad41)") (class "Default")
      (node (ref "U3") (pin "41") (pinfunction "PB5_41") (pintype "bidirectional+no_connect"))
    )
    (net (code "61") (name "unconnected-(U3-PB6-Pad42)") (class "Default")
      (node (ref "U3") (pin "42") (pinfunction "PB6_42") (pintype "bidirectional+no_connect"))
    )
    (net (code "62") (name "unconnected-(U3-PB7-Pad43)") (class "Default")
      (node (ref "U3") (pin "43") (pinfunction "PB7_43") (pintype "bidirectional+no_connect"))
    )
    (net (code "63") (name "unconnected-(U3-PB8-Pad45)") (class "Default")
      (node (ref "U3") (pin "45") (pinfunction "PB8_45") (pintype "bidirectional+no_connect"))
    )
    (net (code "64") (name "unconnected-(U3-PB9-Pad46)") (class "Default")
      (node (ref "U3") (pin "46") (pinfunction "PB9_46") (pintype "bidirectional+no_connect"))
    )
    (net (code "65") (name "unconnected-(U3-PB10-Pad21)") (class "Default")
      (node (ref "U3") (pin "21") (pinfunction "PB10_21") (pintype "bidirectional+no_connect"))
    )
    (net (code "66") (name "unconnected-(U3-PB11-Pad22)") (class "Default")
      (node (ref "U3") (pin "22") (pinfunction "PB11_22") (pintype "bidirectional+no_connect"))
    )
    (net (code "67") (name "unconnected-(U3-PC15-Pad4)") (class "Default")
      (node (ref "U3") (pin "4") (pinfunction "PC15_4") (pintype "bidirectional+no_connect"))
    )
  )
)
